# AMG8833_REV-B.net
KiCad netlist of a schematic drawn in EAGLE
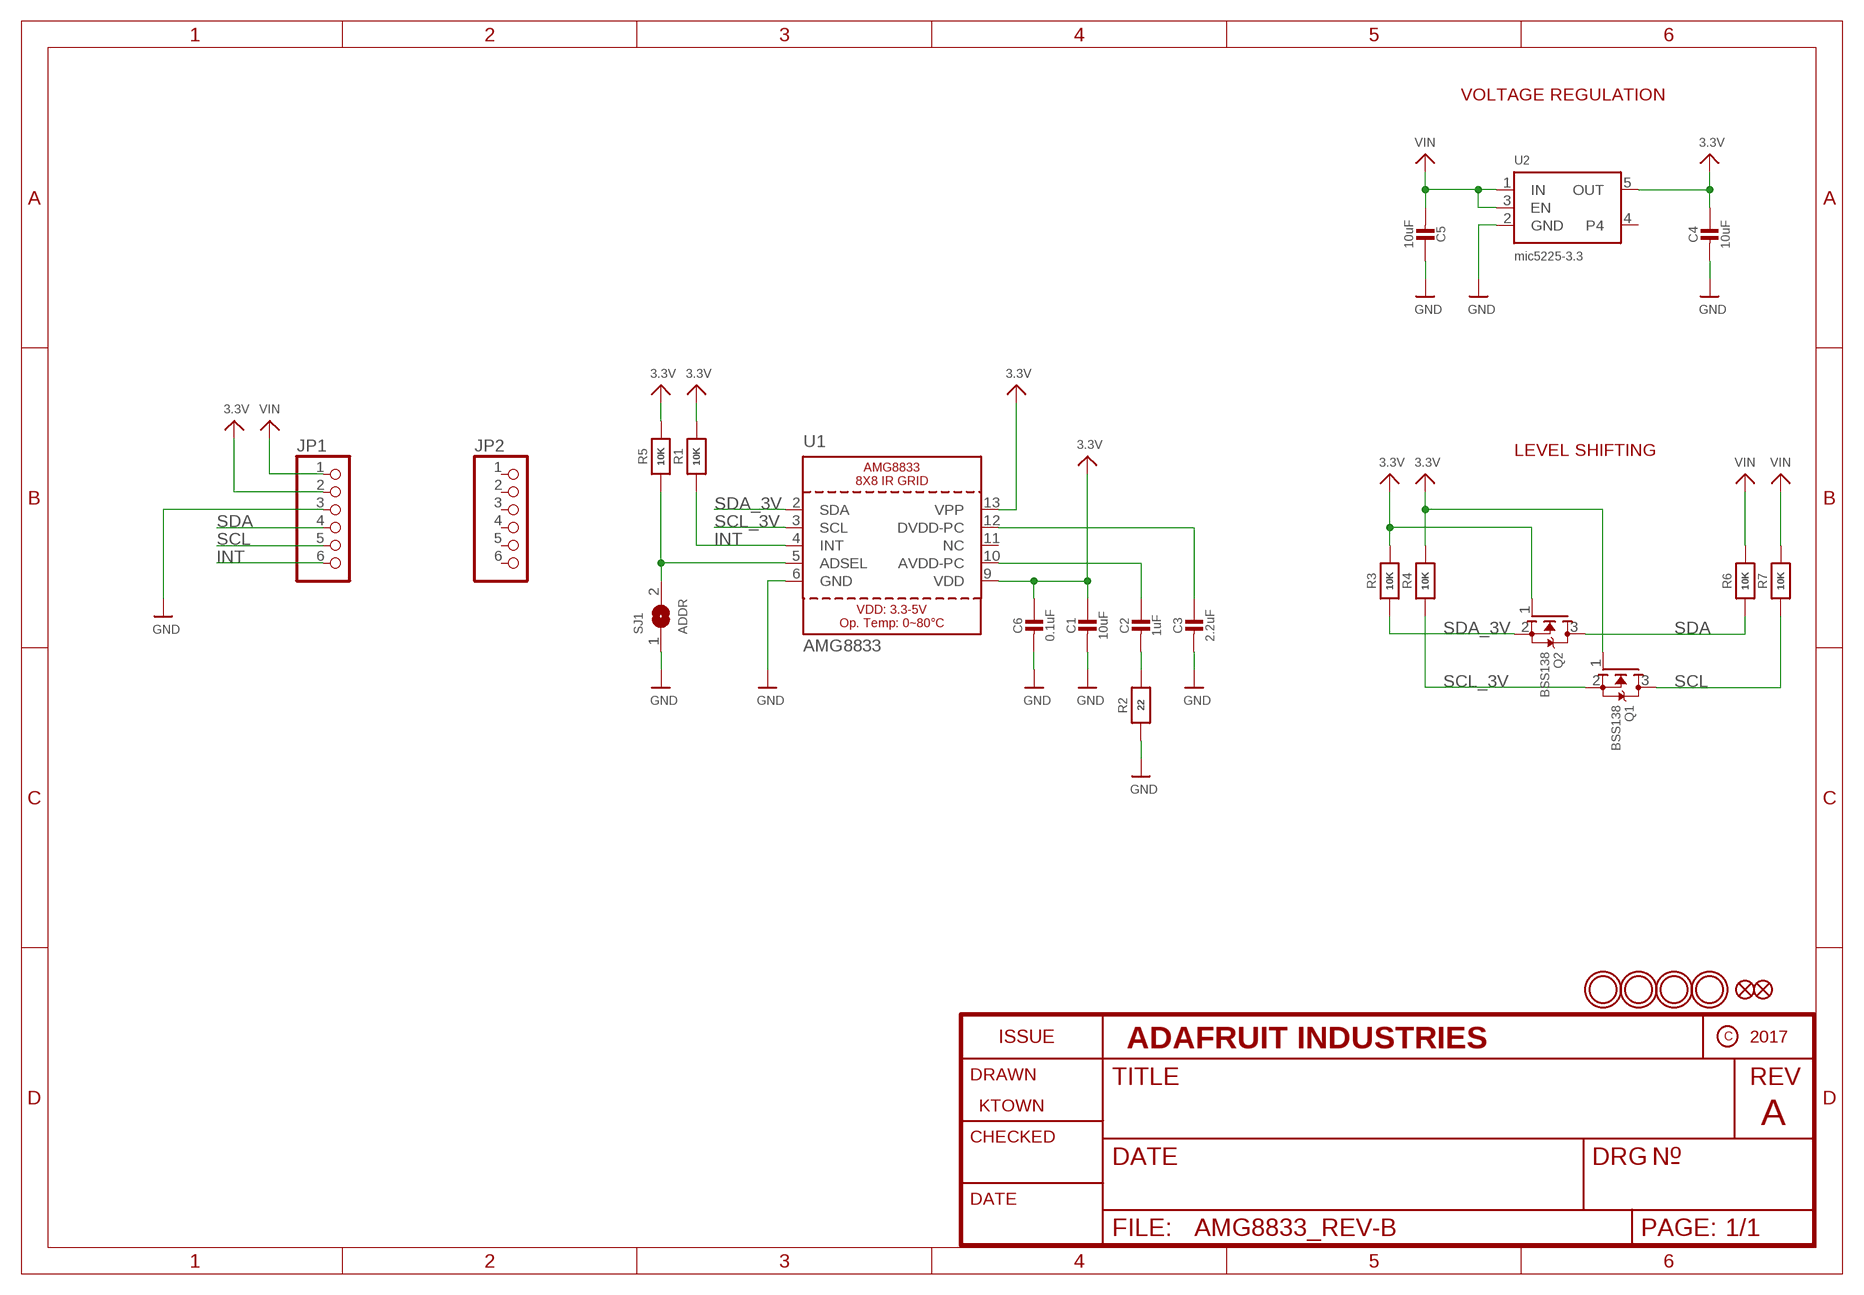
[diagram p0: schematic, sheet 1]

(export (version "E")
  (design (tool "Eeschema 10.0.6"))
  (components
    (comp (ref "C1")
      (value "10uF")
      (footprint "eagle-import:0805-NO")
      (libsource (lib "eagle-import") (part "CAP_CERAMIC0805-NOOUTLINE"))
    )
    (comp (ref "C2")
      (value "1uF")
      (footprint "eagle-import:0805-NO")
      (libsource (lib "eagle-import") (part "CAP_CERAMIC0805-NOOUTLINE"))
    )
    (comp (ref "C3")
      (value "2.2uF")
      (footprint "eagle-import:0805-NO")
      (libsource (lib "eagle-import") (part "CAP_CERAMIC0805-NOOUTLINE"))
    )
    (comp (ref "C4")
      (value "10uF")
      (footprint "eagle-import:0805-NO")
      (libsource (lib "eagle-import") (part "CAP_CERAMIC0805-NOOUTLINE"))
    )
    (comp (ref "C5")
      (value "10uF")
      (footprint "eagle-import:0805-NO")
      (libsource (lib "eagle-import") (part "CAP_CERAMIC0805-NOOUTLINE"))
    )
    (comp (ref "C6")
      (value "0.1uF")
      (footprint "eagle-import:0805-NO")
      (libsource (lib "eagle-import") (part "CAP_CERAMIC0805-NOOUTLINE"))
    )
    (comp (ref "FID2")
      (value "FIDUCIAL_1MM")
      (footprint "eagle-import:FIDUCIAL_1MM")
      (libsource (lib "eagle-import") (part "FIDUCIAL_1MM"))
    )
    (comp (ref "FID3")
      (value "FIDUCIAL_1MM")
      (footprint "eagle-import:FIDUCIAL_1MM")
      (libsource (lib "eagle-import") (part "FIDUCIAL_1MM"))
    )
    (comp (ref "JP1")
      (value "HEADER-1X670MIL")
      (footprint "eagle-import:1X06_ROUND_70")
      (libsource (lib "eagle-import") (part "HEADER-1X670MIL"))
    )
    (comp (ref "JP2")
      (value "HEADER-1X670MIL")
      (footprint "eagle-import:1X06_ROUND_70")
      (libsource (lib "eagle-import") (part "HEADER-1X670MIL"))
    )
    (comp (ref "Q1")
      (value "BSS138")
      (footprint "eagle-import:SOT23-WIDE")
      (libsource (lib "eagle-import") (part "MOSFET-NWIDE"))
    )
    (comp (ref "Q2")
      (value "BSS138")
      (footprint "eagle-import:SOT23-WIDE")
      (libsource (lib "eagle-import") (part "MOSFET-NWIDE"))
    )
    (comp (ref "R1")
      (value "10K")
      (footprint "eagle-import:0805-NO")
      (libsource (lib "eagle-import") (part "RESISTOR0805_NOOUTLINE"))
    )
    (comp (ref "R2")
      (value "22")
      (footprint "eagle-import:0805-NO")
      (libsource (lib "eagle-import") (part "RESISTOR0805_NOOUTLINE"))
    )
    (comp (ref "R3")
      (value "10K")
      (footprint "eagle-import:0805-NO")
      (libsource (lib "eagle-import") (part "RESISTOR0805_NOOUTLINE"))
    )
    (comp (ref "R4")
      (value "10K")
      (footprint "eagle-import:0805-NO")
      (libsource (lib "eagle-import") (part "RESISTOR0805_NOOUTLINE"))
    )
    (comp (ref "R5")
      (value "10K")
      (footprint "eagle-import:0805-NO")
      (libsource (lib "eagle-import") (part "RESISTOR0805_NOOUTLINE"))
    )
    (comp (ref "R6")
      (value "10K")
      (footprint "eagle-import:0805_10MGAP")
      (libsource (lib "eagle-import") (part "RESISTOR0805_10MGAP"))
    )
    (comp (ref "R7")
      (value "10K")
      (footprint "eagle-import:0805_10MGAP")
      (libsource (lib "eagle-import") (part "RESISTOR0805_10MGAP"))
    )
    (comp (ref "SJ1")
      (value "ADDR")
      (footprint "eagle-import:SOLDERJUMPER_ARROW_NOPASTE")
      (libsource (lib "eagle-import") (part "SOLDERJUMPER"))
    )
    (comp (ref "U$16")
      (value "MOUNTINGHOLE2.5")
      (footprint "eagle-import:MOUNTINGHOLE_2.5_PLATED")
      (libsource (lib "eagle-import") (part "MOUNTINGHOLE2.5"))
    )
    (comp (ref "U$17")
      (value "MOUNTINGHOLE2.5")
      (footprint "eagle-import:MOUNTINGHOLE_2.5_PLATED")
      (libsource (lib "eagle-import") (part "MOUNTINGHOLE2.5"))
    )
    (comp (ref "U$18")
      (value "MOUNTINGHOLE2.5")
      (footprint "eagle-import:MOUNTINGHOLE_2.5_PLATED")
      (libsource (lib "eagle-import") (part "MOUNTINGHOLE2.5"))
    )
    (comp (ref "U$19")
      (value "MOUNTINGHOLE2.5")
      (footprint "eagle-import:MOUNTINGHOLE_2.5_PLATED")
      (libsource (lib "eagle-import") (part "MOUNTINGHOLE2.5"))
    )
    (comp (ref "U1")
      (value "AMG8833")
      (footprint "eagle-import:AMG8833")
      (libsource (lib "eagle-import") (part "AMG8833"))
    )
    (comp (ref "U2")
      (value "mic5225-3.3")
      (footprint "eagle-import:SOT23-5")
      (libsource (lib "eagle-import") (part "VREG_SOT23-5"))
    )
  )
  (nets
    (net (code "1") (name "/INT") (class "Default")
      (node (ref "JP1") (pin "6") (pinfunction "6_6") (pintype "passive"))
      (node (ref "R1") (pin "1") (pinfunction "1_1") (pintype "passive"))
      (node (ref "U1") (pin "4") (pinfunction "INT_4") (pintype "output"))
    )
    (net (code "2") (name "/SCL") (class "Default")
      (node (ref "JP1") (pin "5") (pinfunction "5_5") (pintype "passive"))
      (node (ref "Q1") (pin "3") (pinfunction "D_3") (pintype "bidirectional"))
      (node (ref "R7") (pin "1") (pinfunction "1_1") (pintype "passive"))
    )
    (net (code "3") (name "/SCL_3V") (class "Default")
      (node (ref "Q1") (pin "2") (pinfunction "S_2") (pintype "bidirectional"))
      (node (ref "R4") (pin "1") (pinfunction "1_1") (pintype "passive"))
      (node (ref "U1") (pin "3") (pinfunction "SCL_3") (pintype "bidirectional"))
    )
    (net (code "4") (name "/SDA") (class "Default")
      (node (ref "JP1") (pin "4") (pinfunction "4_4") (pintype "passive"))
      (node (ref "Q2") (pin "3") (pinfunction "D_3") (pintype "bidirectional"))
      (node (ref "R6") (pin "1") (pinfunction "1_1") (pintype "passive"))
    )
    (net (code "5") (name "/SDA_3V") (class "Default")
      (node (ref "Q2") (pin "2") (pinfunction "S_2") (pintype "bidirectional"))
      (node (ref "R3") (pin "1") (pinfunction "1_1") (pintype "passive"))
      (node (ref "U1") (pin "2") (pinfunction "SDA_2") (pintype "bidirectional"))
    )
    (net (code "6") (name "3.3V") (class "Default")
      (node (ref "C1") (pin "1") (pinfunction "1_1") (pintype "passive"))
      (node (ref "C4") (pin "1") (pinfunction "1_1") (pintype "passive"))
      (node (ref "C6") (pin "1") (pinfunction "1_1") (pintype "passive"))
      (node (ref "JP1") (pin "2") (pinfunction "2_2") (pintype "passive"))
      (node (ref "Q1") (pin "1") (pinfunction "G_1") (pintype "bidirectional"))
      (node (ref "Q2") (pin "1") (pinfunction "G_1") (pintype "bidirectional"))
      (node (ref "R1") (pin "2") (pinfunction "2_2") (pintype "passive"))
      (node (ref "R3") (pin "2") (pinfunction "2_2") (pintype "passive"))
      (node (ref "R4") (pin "2") (pinfunction "2_2") (pintype "passive"))
      (node (ref "R5") (pin "2") (pinfunction "2_2") (pintype "passive"))
      (node (ref "U1") (pin "13") (pinfunction "VPP_13") (pintype "power_in"))
      (node (ref "U1") (pin "9") (pinfunction "VDD_9") (pintype "power_in"))
      (node (ref "U2") (pin "5") (pinfunction "OUT_5") (pintype "power_in"))
    )
    (net (code "7") (name "GND") (class "Default")
      (node (ref "C1") (pin "2") (pinfunction "2_2") (pintype "passive"))
      (node (ref "C3") (pin "2") (pinfunction "2_2") (pintype "passive"))
      (node (ref "C4") (pin "2") (pinfunction "2_2") (pintype "passive"))
      (node (ref "C5") (pin "1") (pinfunction "1_1") (pintype "passive"))
      (node (ref "C6") (pin "2") (pinfunction "2_2") (pintype "passive"))
      (node (ref "JP1") (pin "3") (pinfunction "3_3") (pintype "passive"))
      (node (ref "R2") (pin "1") (pinfunction "1_1") (pintype "passive"))
      (node (ref "SJ1") (pin "1") (pinfunction "1_1") (pintype "passive"))
      (node (ref "U1") (pin "6") (pinfunction "GND_6") (pintype "power_in"))
      (node (ref "U2") (pin "2") (pinfunction "GND_2") (pintype "power_in"))
    )
    (net (code "8") (name "Net-(C2-Pad2)") (class "Default")
      (node (ref "C2") (pin "2") (pinfunction "2_2") (pintype "passive"))
      (node (ref "R2") (pin "2") (pinfunction "2_2") (pintype "passive"))
    )
    (net (code "9") (name "Net-(U1-ADSEL)") (class "Default")
      (node (ref "R5") (pin "1") (pinfunction "1_1") (pintype "passive"))
      (node (ref "SJ1") (pin "2") (pinfunction "2_2") (pintype "passive"))
      (node (ref "U1") (pin "5") (pinfunction "ADSEL_5") (pintype "input"))
    )
    (net (code "10") (name "Net-(U1-AVDD-PC)") (class "Default")
      (node (ref "C2") (pin "1") (pinfunction "1_1") (pintype "passive"))
      (node (ref "U1") (pin "10") (pinfunction "AVDD-PC_10") (pintype "power_in"))
    )
    (net (code "11") (name "Net-(U1-DVDD-PC)") (class "Default")
      (node (ref "C3") (pin "1") (pinfunction "1_1") (pintype "passive"))
      (node (ref "U1") (pin "12") (pinfunction "DVDD-PC_12") (pintype "power_in"))
    )
    (net (code "12") (name "VIN") (class "Default")
      (node (ref "C5") (pin "2") (pinfunction "2_2") (pintype "passive"))
      (node (ref "JP1") (pin "1") (pinfunction "1_1") (pintype "passive"))
      (node (ref "R6") (pin "2") (pinfunction "2_2") (pintype "passive"))
      (node (ref "R7") (pin "2") (pinfunction "2_2") (pintype "passive"))
      (node (ref "U2") (pin "1") (pinfunction "IN_1") (pintype "power_in"))
      (node (ref "U2") (pin "3") (pinfunction "EN_3") (pintype "input"))
    )
    (net (code "13") (name "unconnected-(JP2-Pad1)") (class "Default")
      (node (ref "JP2") (pin "1") (pinfunction "1_1") (pintype "passive"))
    )
    (net (code "14") (name "unconnected-(JP2-Pad2)") (class "Default")
      (node (ref "JP2") (pin "2") (pinfunction "2_2") (pintype "passive"))
    )
    (net (code "15") (name "unconnected-(JP2-Pad3)") (class "Default")
      (node (ref "JP2") (pin "3") (pinfunction "3_3") (pintype "passive"))
    )
    (net (code "16") (name "unconnected-(JP2-Pad4)") (class "Default")
      (node (ref "JP2") (pin "4") (pinfunction "4_4") (pintype "passive"))
    )
    (net (code "17") (name "unconnected-(JP2-Pad5)") (class "Default")
      (node (ref "JP2") (pin "5") (pinfunction "5_5") (pintype "passive"))
    )
    (net (code "18") (name "unconnected-(JP2-Pad6)") (class "Default")
      (node (ref "JP2") (pin "6") (pinfunction "6_6") (pintype "passive"))
    )
    (net (code "19") (name "unconnected-(U1-NC-Pad11)") (class "Default")
      (node (ref "U1") (pin "11") (pinfunction "NC_11") (pintype "bidirectional"))
    )
    (net (code "20") (name "unconnected-(U2-P4-Pad4)") (class "Default")
      (node (ref "U2") (pin "4") (pinfunction "P4_4") (pintype "bidirectional"))
    )
  )
)
